# GNNS_Module.net
KiCad netlist of a schematic drawn in Altium Designer
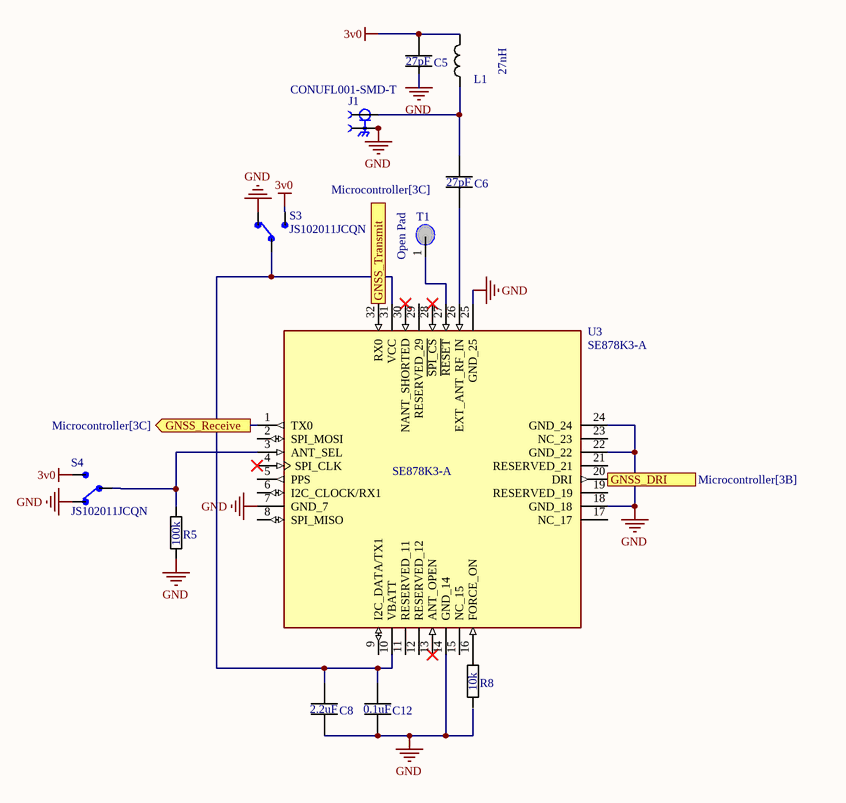
[diagram p0: GNNS_Module.SchDoc]

(export (version "E")
  (design (tool "Eeschema 10.0.6"))
  (components
    (comp (ref "C5")
      (value "27pF")
      (footprint "0603 (Capacitor)")
      (description "Capacitor 12pF 0603 +/-2%")
      (fields
        (field (name "MANUFACTURER") "Murata")
        (field (name "MANUFACTURER PARTNO") "GQM1875C2E120GB12D")
      )
      (libsource (lib "Passives") (part "C-p-012.000-2-0603"))
    )
    (comp (ref "C6")
      (value "27pF")
      (footprint "0603 (Capacitor)")
      (description "Capacitor 12pF 0603 +/-2%")
      (fields
        (field (name "MANUFACTURER") "Murata")
        (field (name "MANUFACTURER PARTNO") "GQM1875C2E120GB12D")
      )
      (libsource (lib "Passives") (part "C-p-012.000-2-0603"))
    )
    (comp (ref "C8")
      (value "2.2uF")
      (footprint "0603 (Capacitor)")
      (description "Capacitor 2.2uF 0603 +/-5%")
      (fields
        (field (name "MANUFACTURER") "Murata")
        (field (name "MANUFACTURER PARTNO") "GRM1885C1H103JA01D")
      )
      (libsource (lib "Passives") (part "C-n-010.000-5-0603"))
    )
    (comp (ref "C12")
      (value "0.1uF")
      (footprint "0603 (Capacitor)")
      (description "Capacitor 0.1uF 0603 +/-5%")
      (fields
        (field (name "MANUFACTURER") "Murata")
        (field (name "MANUFACTURER PARTNO") "GCM1885C2A102JA16D")
      )
      (libsource (lib "Passives") (part "C-n-001.000-5-0603"))
    )
    (comp (ref "J1")
      (value "CONUFL001-SMD-T")
      (footprint "Antenna- CONUFL001-SMD-T")
      (libsource (lib "CONUFL001-SMD-T") (part "CONUFL001-SMD-T"))
    )
    (comp (ref "L1")
      (value "27nH")
      (footprint "PcbLib:4426R-9")
      (description "Inductor 27nH 0402 +/-5%")
      (fields (field (name "MANUFACTURER") "Murata") (field (name "MANUFACTURER PARTNO") "LQG15HS27NJ02D"))
      (libsource (lib "Passives") (part "L-n-027.000-5-0402"))
    )
    (comp (ref "R5")
      (value "100k")
      (footprint "0603 (Resistor)")
      (description "Resistor 100k 0603 +/-1%")
      (fields
        (field (name "MANUFACTURER") "Vishay Dale")
        (field (name "MANUFACTURER PARTNO") "CRCW0603100KFKEAHP")
      )
      (libsource (lib "Passives") (part "R-k-100.000-1-0603"))
    )
    (comp (ref "R8")
      (value "10k")
      (footprint "0603 (Resistor)")
      (description "Resistor 10k 0603 +/-1%")
      (fields
        (field (name "MANUFACTURER") "Vishay Dale")
        (field (name "MANUFACTURER PARTNO") "CRCW060310K0FKEAHP")
      )
      (libsource (lib "Passives") (part "R-k-010.000-1-0603"))
    )
    (comp (ref "S3")
      (value "JS102011JCQN")
      (footprint "SW_JS102011JCQN")
      (description "Switch Slide Spdt 300ma 6v")
      (libsource (lib "JS102011JCQN") (part "JS102011JCQN"))
    )
    (comp (ref "S4")
      (value "JS102011JCQN")
      (footprint "SW_JS102011JCQN")
      (description "Switch Slide Spdt 300ma 6v")
      (libsource (lib "JS102011JCQN") (part "JS102011JCQN"))
    )
    (comp (ref "T1") (value "Open Pad") (footprint "Open Pad") (libsource (lib "Schlib") (part "Open Pad")))
    (comp (ref "U3")
      (value "SE878K3-A")
      (footprint "GNSS Module")
      (description "GNSS L1 Antenna module (GPS, Galileo, Glonass, BeiDou)")
      (fields (field (name "MF") "Telit"))
      (libsource (lib "SE878K3-A") (part "SE878K3-A"))
    )
  )
  (nets
    (net (code "1") (name "/GNSS_DRI") (class "Default")
      (node (ref "U3") (pin "20") (pinfunction "DRI_20") (pintype "output"))
    )
    (net (code "2") (name "/GNSS_Receive") (class "Default")
      (node (ref "U3") (pin "1") (pinfunction "TX0_1") (pintype "output"))
    )
    (net (code "3") (name "/GNSS_Transmit") (class "Default")
      (node (ref "U3") (pin "32") (pinfunction "RX0_32") (pintype "input"))
    )
    (net (code "4") (name "3v0") (class "Default")
      (node (ref "C5") (pin "1") (pinfunction "1_1") (pintype "passive"))
      (node (ref "L1") (pin "1") (pinfunction "1_1") (pintype "passive"))
      (node (ref "S3") (pin "3") (pinfunction "3_3") (pintype "passive"))
      (node (ref "S4") (pin "3") (pinfunction "3_3") (pintype "passive"))
    )
    (net (code "5") (name "GND") (class "Default")
      (node (ref "C12") (pin "2") (pinfunction "2_2") (pintype "passive"))
      (node (ref "C5") (pin "2") (pinfunction "2_2") (pintype "passive"))
      (node (ref "C8") (pin "2") (pinfunction "2_2") (pintype "passive"))
      (node (ref "J1") (pin "2") (pinfunction "2_2") (pintype "passive"))
      (node (ref "J1") (pin "3") (pinfunction "2_3") (pintype "passive"))
      (node (ref "R5") (pin "2") (pinfunction "2_2") (pintype "passive"))
      (node (ref "S3") (pin "1") (pinfunction "1_1") (pintype "passive"))
      (node (ref "S4") (pin "1") (pinfunction "1_1") (pintype "passive"))
      (node (ref "U3") (pin "14") (pinfunction "GND_14_14") (pintype "power_in"))
      (node (ref "U3") (pin "18") (pinfunction "GND_18_18") (pintype "power_in"))
      (node (ref "U3") (pin "22") (pinfunction "GND_22_22") (pintype "power_in"))
      (node (ref "U3") (pin "24") (pinfunction "GND_24_24") (pintype "power_in"))
      (node (ref "U3") (pin "25") (pinfunction "GND_25_25") (pintype "power_in"))
      (node (ref "U3") (pin "7") (pinfunction "GND_7_7") (pintype "power_in"))
    )
    (net (code "6") (name "Net-(C6-Pad1)") (class "Default")
      (node (ref "C6") (pin "1") (pinfunction "1_1") (pintype "passive"))
      (node (ref "J1") (pin "1") (pinfunction "1_1") (pintype "passive"))
      (node (ref "L1") (pin "2") (pinfunction "2_2") (pintype "passive"))
    )
    (net (code "7") (name "Net-(U3-ANT_SEL)") (class "Default")
      (node (ref "R5") (pin "1") (pinfunction "1_1") (pintype "passive"))
      (node (ref "S4") (pin "2") (pinfunction "2_2") (pintype "passive"))
      (node (ref "U3") (pin "3") (pinfunction "ANT_SEL_3") (pintype "input"))
    )
    (net (code "8") (name "Net-(U3-EXT_ANT_RF_IN)") (class "Default")
      (node (ref "C6") (pin "2") (pinfunction "2_2") (pintype "passive"))
      (node (ref "U3") (pin "26") (pinfunction "EXT_ANT_RF_IN_26") (pintype "input"))
    )
    (net (code "9") (name "Net-(U3-FORCE_ON)") (class "Default")
      (node (ref "R8") (pin "1") (pinfunction "1_1") (pintype "passive"))
      (node (ref "U3") (pin "16") (pinfunction "FORCE_ON_16") (pintype "input"))
    )
    (net (code "10") (name "Net-(U3-VBATT)") (class "Default")
      (node (ref "C12") (pin "1") (pinfunction "1_1") (pintype "passive"))
      (node (ref "C8") (pin "1") (pinfunction "1_1") (pintype "passive"))
      (node (ref "S3") (pin "2") (pinfunction "2_2") (pintype "passive"))
      (node (ref "U3") (pin "10") (pinfunction "VBATT_10") (pintype "power_in"))
      (node (ref "U3") (pin "31") (pinfunction "VCC_31") (pintype "power_in"))
    )
    (net (code "11") (name "Net-(U3-~{RESET})") (class "Default")
      (node (ref "T1") (pin "1") (pintype "passive"))
      (node (ref "U3") (pin "27") (pinfunction "~{RESET}_27") (pintype "input"))
    )
    (net (code "12") (name "unconnected-(R8-Pad2)") (class "Default")
      (node (ref "R8") (pin "2") (pinfunction "2_2") (pintype "passive"))
    )
    (net (code "13") (name "unconnected-(U3-ANT_OPEN-Pad13)") (class "Default")
      (node (ref "U3") (pin "13") (pinfunction "ANT_OPEN_13") (pintype "input+no_connect"))
    )
    (net (code "14") (name "unconnected-(U3-I2C_CLOCK{slash}RX1-Pad6)") (class "Default")
      (node (ref "U3") (pin "6") (pinfunction "I2C_CLOCK/RX1_6") (pintype "bidirectional"))
    )
    (net (code "15") (name "unconnected-(U3-I2C_DATA{slash}TX1-Pad9)") (class "Default")
      (node (ref "U3") (pin "9") (pinfunction "I2C_DATA/TX1_9") (pintype "bidirectional"))
    )
    (net (code "16") (name "unconnected-(U3-NANT_SHORTED-Pad30)") (class "Default")
      (node (ref "U3") (pin "30") (pinfunction "NANT_SHORTED_30") (pintype "input+no_connect"))
    )
    (net (code "17") (name "unconnected-(U3-NC_15-Pad15)") (class "Default")
      (node (ref "U3") (pin "15") (pinfunction "NC_15_15") (pintype "passive"))
    )
    (net (code "18") (name "unconnected-(U3-NC_17-Pad17)") (class "Default")
      (node (ref "U3") (pin "17") (pinfunction "NC_17_17") (pintype "passive"))
    )
    (net (code "19") (name "unconnected-(U3-NC_23-Pad23)") (class "Default")
      (node (ref "U3") (pin "23") (pinfunction "NC_23_23") (pintype "passive"))
    )
    (net (code "20") (name "unconnected-(U3-PPS-Pad5)") (class "Default")
      (node (ref "U3") (pin "5") (pinfunction "PPS_5") (pintype "output"))
    )
    (net (code "21") (name "unconnected-(U3-RESERVED_11-Pad11)") (class "Default")
      (node (ref "U3") (pin "11") (pinfunction "RESERVED_11_11") (pintype "passive"))
    )
    (net (code "22") (name "unconnected-(U3-RESERVED_12-Pad12)") (class "Default")
      (node (ref "U3") (pin "12") (pinfunction "RESERVED_12_12") (pintype "passive"))
    )
    (net (code "23") (name "unconnected-(U3-RESERVED_19-Pad19)") (class "Default")
      (node (ref "U3") (pin "19") (pinfunction "RESERVED_19_19") (pintype "passive"))
    )
    (net (code "24") (name "unconnected-(U3-RESERVED_21-Pad21)") (class "Default")
      (node (ref "U3") (pin "21") (pinfunction "RESERVED_21_21") (pintype "passive"))
    )
    (net (code "25") (name "unconnected-(U3-RESERVED_29-Pad29)") (class "Default")
      (node (ref "U3") (pin "29") (pinfunction "RESERVED_29_29") (pintype "passive"))
    )
    (net (code "26") (name "unconnected-(U3-SPI_CLK-Pad4)") (class "Default")
      (node (ref "U3") (pin "4") (pinfunction "SPI_CLK_4") (pintype "input+no_connect"))
    )
    (net (code "27") (name "unconnected-(U3-SPI_MISO-Pad8)") (class "Default")
      (node (ref "U3") (pin "8") (pinfunction "SPI_MISO_8") (pintype "bidirectional"))
    )
    (net (code "28") (name "unconnected-(U3-SPI_MOSI-Pad2)") (class "Default")
      (node (ref "U3") (pin "2") (pinfunction "SPI_MOSI_2") (pintype "bidirectional"))
    )
    (net (code "29") (name "unconnected-(U3-~{SPI_CS}-Pad28)") (class "Default")
      (node (ref "U3") (pin "28") (pinfunction "~{SPI_CS}_28") (pintype "input+no_connect"))
    )
  )
)
